# Franzino.net
KiCad netlist of a schematic drawn in EAGLE
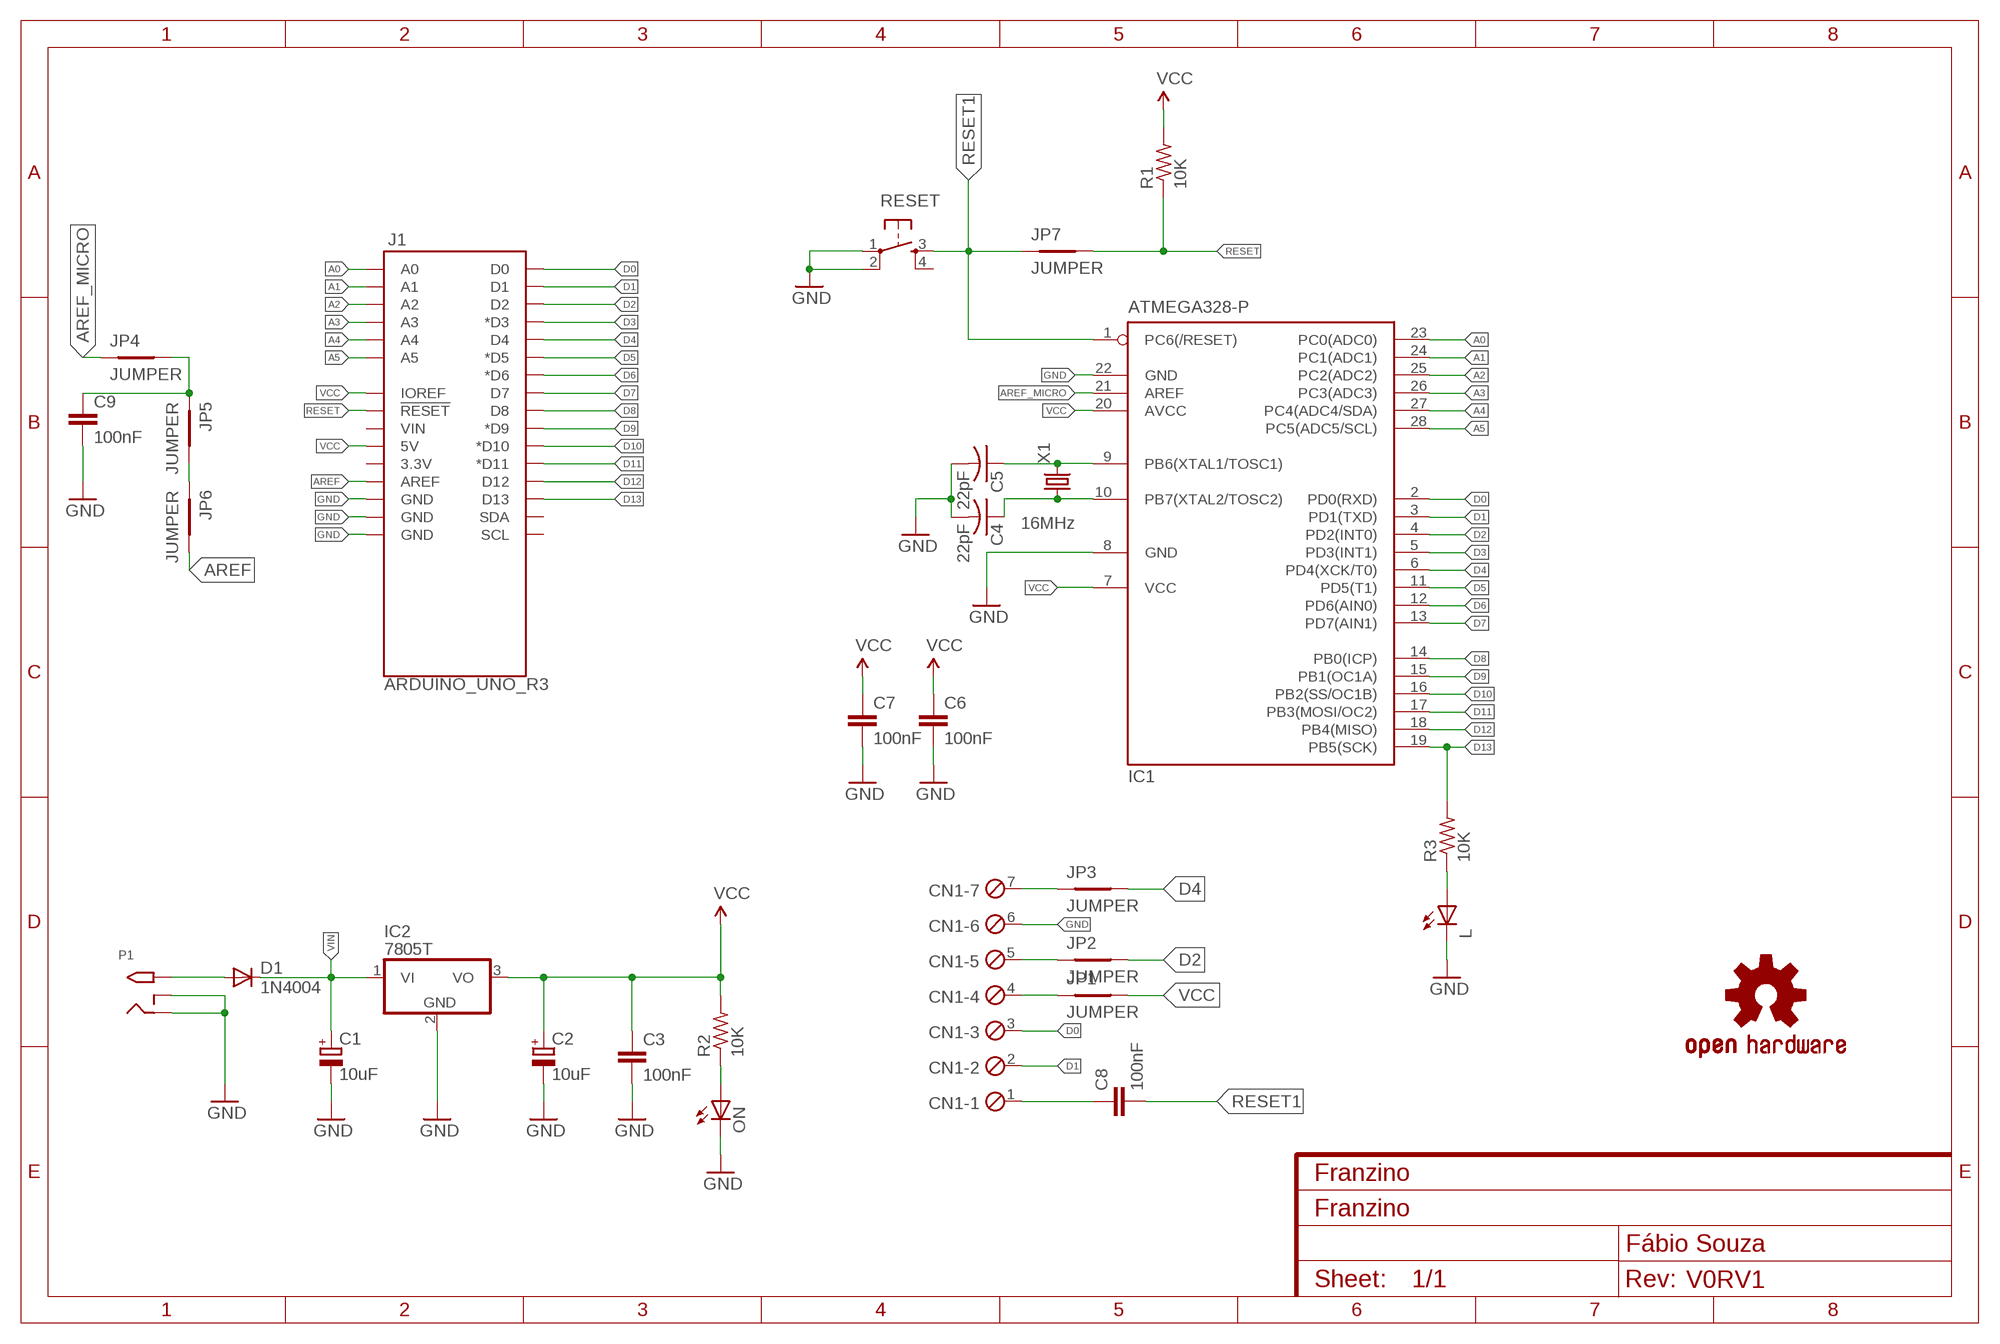
[diagram p0: schematic, sheet 1]

(export (version "E")
  (design (tool "Eeschema 10.0.6"))
  (components
    (comp (ref "C1")
      (value "10uF")
      (footprint "eagle-import:E2,5-6")
      (libsource (lib "eagle-import") (part "CPOL-EUE2.5-6"))
    )
    (comp (ref "C2")
      (value "10uF")
      (footprint "eagle-import:E2,5-6")
      (libsource (lib "eagle-import") (part "CPOL-EUE2.5-6"))
    )
    (comp (ref "C3")
      (value "100nF")
      (footprint "eagle-import:C025-025X050")
      (libsource (lib "eagle-import") (part "C-EU025-025X050"))
    )
    (comp (ref "C4")
      (value "22pF")
      (footprint "eagle-import:C025-024X044")
      (libsource (lib "eagle-import") (part "C-US025-024X044"))
    )
    (comp (ref "C5")
      (value "22pF")
      (footprint "eagle-import:C025-024X044")
      (libsource (lib "eagle-import") (part "C-US025-024X044"))
    )
    (comp (ref "C6")
      (value "100nF")
      (footprint "eagle-import:C025-025X050")
      (libsource (lib "eagle-import") (part "C-EU025-025X050"))
    )
    (comp (ref "C7")
      (value "100nF")
      (footprint "eagle-import:C025-025X050")
      (libsource (lib "eagle-import") (part "C-EU025-025X050"))
    )
    (comp (ref "C8")
      (value "100nF")
      (footprint "eagle-import:C025-025X050")
      (libsource (lib "eagle-import") (part "resistor_348_C-EU025-025X050"))
    )
    (comp (ref "C9")
      (value "100nF")
      (footprint "eagle-import:C025-025X050")
      (libsource (lib "eagle-import") (part "resistor_348_C-EU025-025X050"))
    )
    (comp (ref "CN1")
      (value "BARRA de PINOS 6 VIAS")
      (footprint "eagle-import:7POL254")
      (libsource (lib "eagle-import") (part "MPT7"))
    )
    (comp (ref "D1")
      (value "1N4004")
      (footprint "eagle-import:DO41-10")
      (libsource (lib "eagle-import") (part "1N4004"))
    )
    (comp (ref "IC1")
      (value "ATMEGA328-P")
      (footprint "eagle-import:DIL28-3")
      (libsource (lib "eagle-import") (part "MEGA8-P"))
    )
    (comp (ref "IC2")
      (value "7805T")
      (footprint "eagle-import:TO220H")
      (libsource (lib "eagle-import") (part "78T05"))
    )
    (comp (ref "J1")
      (value "ARDUINO_UNO_R3")
      (footprint "eagle-import:ARDUINO_UNO_R3_PINS")
      (libsource (lib "eagle-import") (part "ARDUINO_UNO_R3"))
    )
    (comp (ref "JP1")
      (value "JUMPER")
      (footprint "eagle-import:JUMP10")
      (libsource (lib "eagle-import") (part "JUMPER"))
    )
    (comp (ref "JP2")
      (value "JUMPER")
      (footprint "eagle-import:JUMP10")
      (libsource (lib "eagle-import") (part "JUMPER"))
    )
    (comp (ref "JP3")
      (value "JUMPER")
      (footprint "eagle-import:JUMP10")
      (libsource (lib "eagle-import") (part "JUMPER"))
    )
    (comp (ref "JP4")
      (value "JUMPER")
      (footprint "eagle-import:JUMP10")
      (libsource (lib "eagle-import") (part "JUMPER"))
    )
    (comp (ref "JP5")
      (value "JUMPER")
      (footprint "eagle-import:JUMP10")
      (libsource (lib "eagle-import") (part "JUMPER"))
    )
    (comp (ref "JP6")
      (value "JUMPER")
      (footprint "eagle-import:JUMP10")
      (libsource (lib "eagle-import") (part "JUMPER"))
    )
    (comp (ref "JP7")
      (value "JUMPER")
      (footprint "eagle-import:JUMP10")
      (libsource (lib "eagle-import") (part "JUMPER"))
    )
    (comp (ref "L")
      (value "LED 3mm Amarelo")
      (footprint "eagle-import:LED3MM")
      (libsource (lib "eagle-import") (part "LED3MM"))
    )
    (comp (ref "LOGO2")
      (value "OSHW-LOGOL")
      (footprint "eagle-import:OSHW-LOGO-L")
      (libsource (lib "eagle-import") (part "OSHW-LOGOL"))
    )
    (comp (ref "ON")
      (value "LED 3 mm VERDE")
      (footprint "eagle-import:LED3MM")
      (libsource (lib "eagle-import") (part "LED3MM"))
    )
    (comp (ref "P1")
      (value "2.1MMJACKTHM")
      (footprint "eagle-import:PJ-102A")
      (libsource (lib "eagle-import") (part "2.1MMJACKTHM"))
    )
    (comp (ref "R1")
      (value "10K")
      (footprint "eagle-import:0207_10")
      (libsource (lib "eagle-import") (part "R-US_0207/10"))
    )
    (comp (ref "R2")
      (value "10K")
      (footprint "eagle-import:0207_10")
      (libsource (lib "eagle-import") (part "R-US_0207/10"))
    )
    (comp (ref "R3")
      (value "10K")
      (footprint "eagle-import:0207_10")
      (libsource (lib "eagle-import") (part "R-US_0207/10"))
    )
    (comp (ref "RESET")
      (value "CHAVE TACTIL 6 mm")
      (footprint "eagle-import:TACTILE-PTH")
      (libsource (lib "eagle-import") (part "TAC_SWITCHPTH"))
    )
    (comp (ref "X1")
      (value "16MHz")
      (footprint "eagle-import:HC49_S")
      (libsource (lib "eagle-import") (part "CRYSTALHC49S"))
    )
  )
  (nets
    (net (code "1") (name "A0") (class "Default")
      (node (ref "IC1") (pin "23") (pinfunction "PC0(ADC0)_23") (pintype "bidirectional"))
      (node (ref "J1") (pin "A0") (pinfunction "A0_A0") (pintype "bidirectional"))
    )
    (net (code "2") (name "A1") (class "Default")
      (node (ref "IC1") (pin "24") (pinfunction "PC1(ADC1)_24") (pintype "bidirectional"))
      (node (ref "J1") (pin "A1") (pinfunction "A1_A1") (pintype "bidirectional"))
    )
    (net (code "3") (name "A2") (class "Default")
      (node (ref "IC1") (pin "25") (pinfunction "PC2(ADC2)_25") (pintype "bidirectional"))
      (node (ref "J1") (pin "A2") (pinfunction "A2_A2") (pintype "bidirectional"))
    )
    (net (code "4") (name "A3") (class "Default")
      (node (ref "IC1") (pin "26") (pinfunction "PC3(ADC3)_26") (pintype "bidirectional"))
      (node (ref "J1") (pin "A3") (pinfunction "A3_A3") (pintype "bidirectional"))
    )
    (net (code "5") (name "A4") (class "Default")
      (node (ref "IC1") (pin "27") (pinfunction "PC4(ADC4/SDA)_27") (pintype "bidirectional"))
      (node (ref "J1") (pin "A4") (pinfunction "A4_A4") (pintype "bidirectional"))
    )
    (net (code "6") (name "A5") (class "Default")
      (node (ref "IC1") (pin "28") (pinfunction "PC5(ADC5/SCL)_28") (pintype "bidirectional"))
      (node (ref "J1") (pin "A5") (pinfunction "A5_A5") (pintype "bidirectional"))
    )
    (net (code "7") (name "AREF") (class "Default")
      (node (ref "J1") (pin "AREF") (pinfunction "AREF_AREF") (pintype "bidirectional"))
      (node (ref "JP6") (pin "2") (pinfunction "2_2") (pintype "passive"))
    )
    (net (code "8") (name "AREF_MICRO") (class "Default")
      (node (ref "IC1") (pin "21") (pinfunction "AREF_21") (pintype "passive"))
      (node (ref "JP4") (pin "1") (pinfunction "1_1") (pintype "passive"))
    )
    (net (code "9") (name "D0") (class "Default")
      (node (ref "CN1") (pin "3") (pinfunction "1_3") (pintype "passive"))
      (node (ref "IC1") (pin "2") (pinfunction "PD0(RXD)_2") (pintype "bidirectional"))
      (node (ref "J1") (pin "D0") (pinfunction "D0_D0") (pintype "bidirectional"))
    )
    (net (code "10") (name "D1") (class "Default")
      (node (ref "CN1") (pin "2") (pinfunction "1_2") (pintype "passive"))
      (node (ref "IC1") (pin "3") (pinfunction "PD1(TXD)_3") (pintype "bidirectional"))
      (node (ref "J1") (pin "D1") (pinfunction "D1_D1") (pintype "bidirectional"))
    )
    (net (code "11") (name "D2") (class "Default")
      (node (ref "IC1") (pin "4") (pinfunction "PD2(INT0)_4") (pintype "bidirectional"))
      (node (ref "J1") (pin "D2") (pinfunction "D2_D2") (pintype "bidirectional"))
      (node (ref "JP2") (pin "2") (pinfunction "2_2") (pintype "passive"))
    )
    (net (code "12") (name "D3") (class "Default")
      (node (ref "IC1") (pin "5") (pinfunction "PD3(INT1)_5") (pintype "bidirectional"))
      (node (ref "J1") (pin "D3") (pinfunction "*D3_D3") (pintype "bidirectional"))
    )
    (net (code "13") (name "D4") (class "Default")
      (node (ref "IC1") (pin "6") (pinfunction "PD4(XCK/T0)_6") (pintype "bidirectional"))
      (node (ref "J1") (pin "D4") (pinfunction "D4_D4") (pintype "bidirectional"))
      (node (ref "JP3") (pin "2") (pinfunction "2_2") (pintype "passive"))
    )
    (net (code "14") (name "D5") (class "Default")
      (node (ref "IC1") (pin "11") (pinfunction "PD5(T1)_11") (pintype "bidirectional"))
      (node (ref "J1") (pin "D5") (pinfunction "*D5_D5") (pintype "bidirectional"))
    )
    (net (code "15") (name "D6") (class "Default")
      (node (ref "IC1") (pin "12") (pinfunction "PD6(AIN0)_12") (pintype "bidirectional"))
      (node (ref "J1") (pin "D6") (pinfunction "*D6_D6") (pintype "bidirectional"))
    )
    (net (code "16") (name "D7") (class "Default")
      (node (ref "IC1") (pin "13") (pinfunction "PD7(AIN1)_13") (pintype "bidirectional"))
      (node (ref "J1") (pin "D7") (pinfunction "D7_D7") (pintype "bidirectional"))
    )
    (net (code "17") (name "D8") (class "Default")
      (node (ref "IC1") (pin "14") (pinfunction "PB0(ICP)_14") (pintype "bidirectional"))
      (node (ref "J1") (pin "D8") (pinfunction "D8_D8") (pintype "bidirectional"))
    )
    (net (code "18") (name "D9") (class "Default")
      (node (ref "IC1") (pin "15") (pinfunction "PB1(OC1A)_15") (pintype "bidirectional"))
      (node (ref "J1") (pin "D9") (pinfunction "*D9_D9") (pintype "bidirectional"))
    )
    (net (code "19") (name "D10") (class "Default")
      (node (ref "IC1") (pin "16") (pinfunction "PB2(SS/OC1B)_16") (pintype "bidirectional"))
      (node (ref "J1") (pin "D10") (pinfunction "*D10_D10") (pintype "bidirectional"))
    )
    (net (code "20") (name "D11") (class "Default")
      (node (ref "IC1") (pin "17") (pinfunction "PB3(MOSI/OC2)_17") (pintype "bidirectional"))
      (node (ref "J1") (pin "D11") (pinfunction "*D11_D11") (pintype "bidirectional"))
    )
    (net (code "21") (name "D12") (class "Default")
      (node (ref "IC1") (pin "18") (pinfunction "PB4(MISO)_18") (pintype "bidirectional"))
      (node (ref "J1") (pin "D12") (pinfunction "D12_D12") (pintype "bidirectional"))
    )
    (net (code "22") (name "D13") (class "Default")
      (node (ref "IC1") (pin "19") (pinfunction "PB5(SCK)_19") (pintype "bidirectional"))
      (node (ref "J1") (pin "D13") (pinfunction "D13_D13") (pintype "bidirectional"))
      (node (ref "R3") (pin "2") (pinfunction "2_2") (pintype "passive"))
    )
    (net (code "23") (name "GND") (class "Default")
      (node (ref "C1") (pin "-") (pinfunction "-_-") (pintype "passive"))
      (node (ref "C2") (pin "-") (pinfunction "-_-") (pintype "passive"))
      (node (ref "C3") (pin "2") (pinfunction "2_2") (pintype "passive"))
      (node (ref "C4") (pin "2") (pinfunction "2_2") (pintype "passive"))
      (node (ref "C5") (pin "2") (pinfunction "2_2") (pintype "passive"))
      (node (ref "C6") (pin "2") (pinfunction "2_2") (pintype "passive"))
      (node (ref "C7") (pin "2") (pinfunction "2_2") (pintype "passive"))
      (node (ref "C9") (pin "2") (pinfunction "2_2") (pintype "passive"))
      (node (ref "CN1") (pin "6") (pinfunction "1_6") (pintype "passive"))
      (node (ref "IC1") (pin "22") (pinfunction "GND_22") (pintype "power_in"))
      (node (ref "IC1") (pin "8") (pinfunction "GND_8") (pintype "power_in"))
      (node (ref "IC2") (pin "2") (pinfunction "GND_2") (pintype "passive"))
      (node (ref "J1") (pin "GND@1") (pinfunction "GND_GND@1") (pintype "bidirectional"))
      (node (ref "J1") (pin "GND@2") (pinfunction "GND_GND@2") (pintype "bidirectional"))
      (node (ref "J1") (pin "GND@3") (pinfunction "GND_GND@3") (pintype "bidirectional"))
      (node (ref "L") (pin "K") (pinfunction "C_K") (pintype "passive"))
      (node (ref "ON") (pin "K") (pinfunction "C_K") (pintype "passive"))
      (node (ref "P1") (pin "RING") (pinfunction "RING_RING") (pintype "bidirectional"))
      (node (ref "P1") (pin "RING_SW") (pinfunction "RING_SW_RING_SW") (pintype "bidirectional"))
      (node (ref "RESET") (pin "1") (pinfunction "1_1") (pintype "passive"))
      (node (ref "RESET") (pin "2") (pinfunction "2_2") (pintype "passive"))
    )
    (net (code "24") (name "Net-(C8-Pad1)") (class "Default")
      (node (ref "C8") (pin "1") (pinfunction "1_1") (pintype "passive"))
      (node (ref "CN1") (pin "1") (pinfunction "1_1") (pintype "passive"))
    )
    (net (code "25") (name "Net-(C9-Pad1)") (class "Default")
      (node (ref "C9") (pin "1") (pinfunction "1_1") (pintype "passive"))
      (node (ref "JP4") (pin "2") (pinfunction "2_2") (pintype "passive"))
      (node (ref "JP5") (pin "1") (pinfunction "1_1") (pintype "passive"))
    )
    (net (code "26") (name "Net-(CN1D-1)") (class "Default")
      (node (ref "CN1") (pin "4") (pinfunction "1_4") (pintype "passive"))
      (node (ref "JP1") (pin "1") (pinfunction "1_1") (pintype "passive"))
    )
    (net (code "27") (name "Net-(CN1E-1)") (class "Default")
      (node (ref "CN1") (pin "5") (pinfunction "1_5") (pintype "passive"))
      (node (ref "JP2") (pin "1") (pinfunction "1_1") (pintype "passive"))
    )
    (net (code "28") (name "Net-(CN1G-1)") (class "Default")
      (node (ref "CN1") (pin "7") (pinfunction "1_7") (pintype "passive"))
      (node (ref "JP3") (pin "1") (pinfunction "1_1") (pintype "passive"))
    )
    (net (code "29") (name "Net-(D1-PadA)") (class "Default")
      (node (ref "D1") (pin "A") (pinfunction "A_A") (pintype "passive"))
      (node (ref "P1") (pin "TIP") (pinfunction "TIP_TIP") (pintype "bidirectional"))
    )
    (net (code "30") (name "Net-(IC1-PB6(XTAL1{slash}TOSC1))") (class "Default")
      (node (ref "C5") (pin "1") (pinfunction "1_1") (pintype "passive"))
      (node (ref "IC1") (pin "9") (pinfunction "PB6(XTAL1/TOSC1)_9") (pintype "bidirectional"))
      (node (ref "X1") (pin "2") (pinfunction "2_2") (pintype "passive"))
    )
    (net (code "31") (name "Net-(IC1-PB7(XTAL2{slash}TOSC2))") (class "Default")
      (node (ref "C4") (pin "1") (pinfunction "1_1") (pintype "passive"))
      (node (ref "IC1") (pin "10") (pinfunction "PB7(XTAL2/TOSC2)_10") (pintype "bidirectional"))
      (node (ref "X1") (pin "1") (pinfunction "1_1") (pintype "passive"))
    )
    (net (code "32") (name "Net-(JP5-Pad2)") (class "Default")
      (node (ref "JP5") (pin "2") (pinfunction "2_2") (pintype "passive"))
      (node (ref "JP6") (pin "1") (pinfunction "1_1") (pintype "passive"))
    )
    (net (code "33") (name "Net-(L-PadA)") (class "Default")
      (node (ref "L") (pin "A") (pinfunction "A_A") (pintype "passive"))
      (node (ref "R3") (pin "1") (pinfunction "1_1") (pintype "passive"))
    )
    (net (code "34") (name "Net-(ON-PadA)") (class "Default")
      (node (ref "ON") (pin "A") (pinfunction "A_A") (pintype "passive"))
      (node (ref "R2") (pin "1") (pinfunction "1_1") (pintype "passive"))
    )
    (net (code "35") (name "RESET") (class "Default")
      (node (ref "J1") (pin "RESET@1") (pinfunction "~{RESET}_RESET@1") (pintype "bidirectional"))
      (node (ref "JP7") (pin "2") (pinfunction "2_2") (pintype "passive"))
      (node (ref "R1") (pin "1") (pinfunction "1_1") (pintype "passive"))
    )
    (net (code "36") (name "RESET1") (class "Default")
      (node (ref "C8") (pin "2") (pinfunction "2_2") (pintype "passive"))
      (node (ref "IC1") (pin "1") (pinfunction "PC6(/RESET)_1") (pintype "bidirectional"))
      (node (ref "JP7") (pin "1") (pinfunction "1_1") (pintype "passive"))
      (node (ref "RESET") (pin "3") (pinfunction "3_3") (pintype "passive"))
    )
    (net (code "37") (name "VCC") (class "Default")
      (node (ref "C2") (pin "+") (pinfunction "+_+") (pintype "passive"))
      (node (ref "C3") (pin "1") (pinfunction "1_1") (pintype "passive"))
      (node (ref "C6") (pin "1") (pinfunction "1_1") (pintype "passive"))
      (node (ref "C7") (pin "1") (pinfunction "1_1") (pintype "passive"))
      (node (ref "IC1") (pin "20") (pinfunction "AVCC_20") (pintype "power_in"))
      (node (ref "IC1") (pin "7") (pinfunction "VCC_7") (pintype "power_in"))
      (node (ref "IC2") (pin "3") (pinfunction "VO_3") (pintype "passive"))
      (node (ref "J1") (pin "5V") (pinfunction "5V_5V") (pintype "bidirectional"))
      (node (ref "J1") (pin "IOREF") (pinfunction "IOREF_IOREF") (pintype "bidirectional"))
      (node (ref "JP1") (pin "2") (pinfunction "2_2") (pintype "passive"))
      (node (ref "R1") (pin "2") (pinfunction "2_2") (pintype "passive"))
      (node (ref "R2") (pin "2") (pinfunction "2_2") (pintype "passive"))
    )
    (net (code "38") (name "VIN") (class "Default")
      (node (ref "C1") (pin "+") (pinfunction "+_+") (pintype "passive"))
      (node (ref "D1") (pin "C") (pinfunction "C_C") (pintype "passive"))
      (node (ref "IC2") (pin "1") (pinfunction "VI_1") (pintype "input"))
    )
    (net (code "39") (name "unconnected-(J1-Pad3.3V)") (class "Default")
      (node (ref "J1") (pin "3.3V") (pinfunction "3.3V_3.3V") (pintype "bidirectional"))
    )
    (net (code "40") (name "unconnected-(J1-PadSCL)") (class "Default")
      (node (ref "J1") (pin "SCL") (pinfunction "SCL_SCL") (pintype "bidirectional"))
    )
    (net (code "41") (name "unconnected-(J1-PadSDA)") (class "Default")
      (node (ref "J1") (pin "SDA") (pinfunction "SDA_SDA") (pintype "bidirectional"))
    )
    (net (code "42") (name "unconnected-(J1-PadVIN)") (class "Default")
      (node (ref "J1") (pin "VIN") (pinfunction "VIN_VIN") (pintype "bidirectional"))
    )
    (net (code "43") (name "unconnected-(RESET-Pad4)") (class "Default")
      (node (ref "RESET") (pin "4") (pinfunction "4_4") (pintype "passive"))
    )
  )
)
